# NU-SYNTHS_MIDICV.net
KiCad netlist of a schematic drawn in Altium Designer
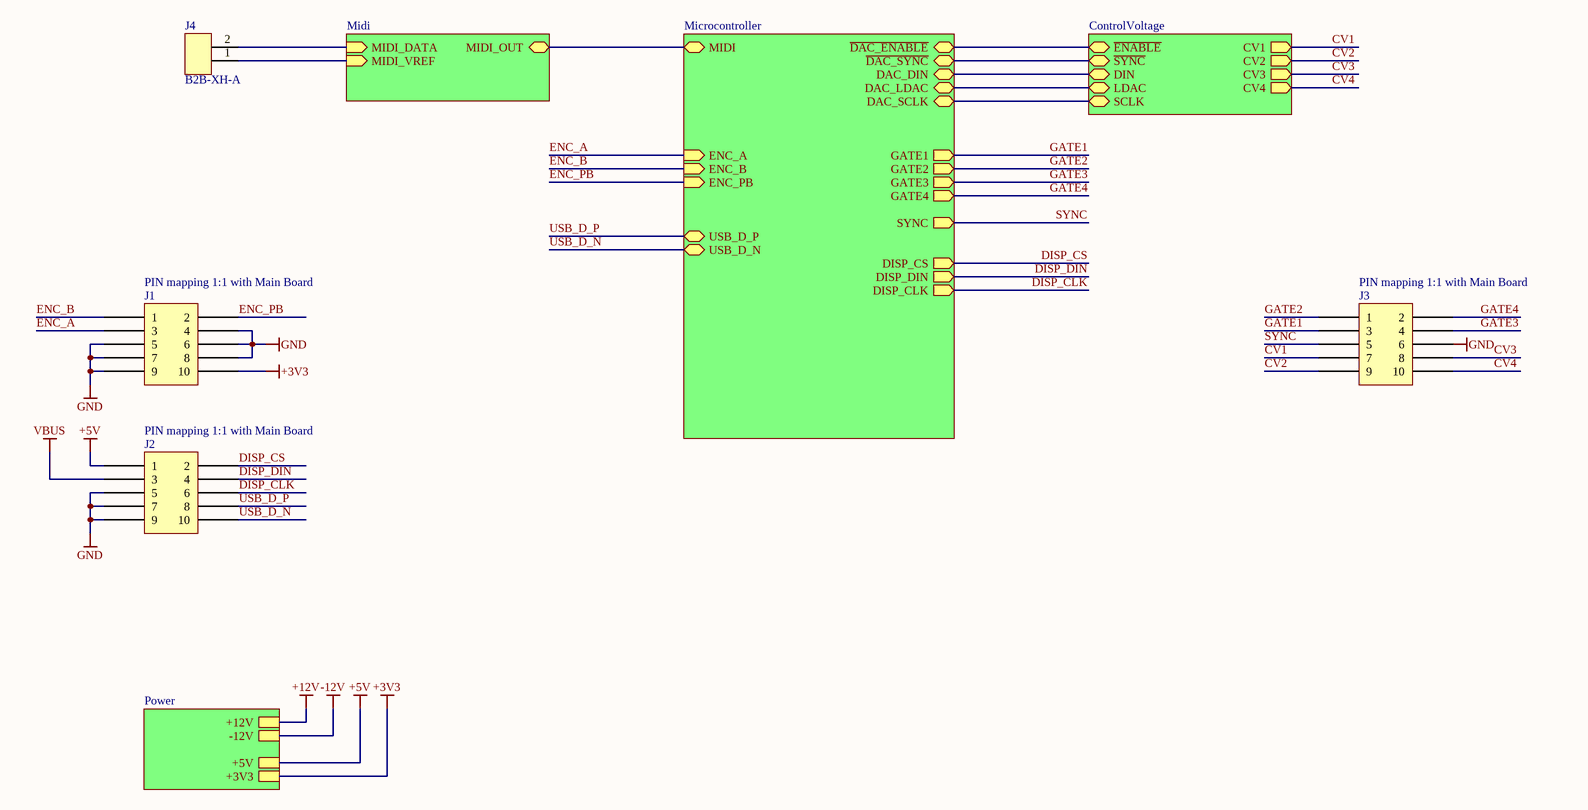
[diagram p0: NU-SYNTHS_MIDICV.SchDoc]

(export (version "E")
  (design (tool "Eeschema 10.0.6"))
  (components
    (comp (ref "J1")
      (value "GENERIC_HEADER_2x5")
      (footprint "HEADER_2x5_TH_FEMALE")
      (description "Generic 2x5 header")
      (libsource (lib "LabratsSynthLib") (part "GENERIC_HEADER_2x5"))
    )
    (comp (ref "J2")
      (value "GENERIC_HEADER_2x5")
      (footprint "HEADER_2x5_TH_FEMALE")
      (description "Generic 2x5 header")
      (libsource (lib "LabratsSynthLib") (part "GENERIC_HEADER_2x5"))
    )
    (comp (ref "J3")
      (value "GENERIC_HEADER_2x5")
      (footprint "HEADER_2x5_TH_FEMALE")
      (description "Generic 2x5 header")
      (libsource (lib "LabratsSynthLib") (part "GENERIC_HEADER_2x5"))
    )
    (comp (ref "J4")
      (value "B2B-XH-A")
      (footprint "JST_HEADER_1x2_SMD_MALE")
      (description "Connector Header Through Hole 2 position 0.098 (2.50mm)")
      (fields (field (name "MF") "JST Sales") (field (name "MP") "B2B-XH-A(LF)(SN)"))
      (libsource (lib "LabratsSynthLib") (part "B2B-XH-A(LF)(SN)"))
    )
  )
  (nets
    (net (code "1") (name "+3V3") (class "Default")
      (node (ref "J1") (pin "10") (pinfunction "10_10") (pintype "passive"))
    )
    (net (code "2") (name "+5V") (class "Default")
      (node (ref "J2") (pin "1") (pinfunction "1_1") (pintype "passive"))
    )
    (net (code "5") (name "/CV1") (class "Default")
      (node (ref "J3") (pin "7") (pinfunction "7_7") (pintype "passive"))
    )
    (net (code "6") (name "/CV2") (class "Default")
      (node (ref "J3") (pin "9") (pinfunction "9_9") (pintype "passive"))
    )
    (net (code "7") (name "/CV3") (class "Default")
      (node (ref "J3") (pin "8") (pinfunction "8_8") (pintype "passive"))
    )
    (net (code "8") (name "/CV4") (class "Default")
      (node (ref "J3") (pin "10") (pinfunction "10_10") (pintype "passive"))
    )
    (net (code "12") (name "/DISP_CLK") (class "Default")
      (node (ref "J2") (pin "6") (pinfunction "6_6") (pintype "passive"))
    )
    (net (code "13") (name "/DISP_CS") (class "Default")
      (node (ref "J2") (pin "2") (pinfunction "2_2") (pintype "passive"))
    )
    (net (code "14") (name "/DISP_DIN") (class "Default")
      (node (ref "J2") (pin "4") (pinfunction "4_4") (pintype "passive"))
    )
    (net (code "15") (name "/ENC_A") (class "Default")
      (node (ref "J1") (pin "3") (pinfunction "3_3") (pintype "passive"))
    )
    (net (code "16") (name "/ENC_B") (class "Default")
      (node (ref "J1") (pin "1") (pinfunction "1_1") (pintype "passive"))
    )
    (net (code "17") (name "/ENC_PB") (class "Default")
      (node (ref "J1") (pin "2") (pinfunction "2_2") (pintype "passive"))
    )
    (net (code "18") (name "/GATE1") (class "Default")
      (node (ref "J3") (pin "3") (pinfunction "3_3") (pintype "passive"))
    )
    (net (code "19") (name "/GATE2") (class "Default")
      (node (ref "J3") (pin "1") (pinfunction "1_1") (pintype "passive"))
    )
    (net (code "20") (name "/GATE3") (class "Default")
      (node (ref "J3") (pin "4") (pinfunction "4_4") (pintype "passive"))
    )
    (net (code "21") (name "/GATE4") (class "Default")
      (node (ref "J3") (pin "2") (pinfunction "2_2") (pintype "passive"))
    )
    (net (code "23") (name "/MIDI_DATA") (class "Default")
      (node (ref "J4") (pin "2") (pinfunction "2_2") (pintype "passive"))
    )
    (net (code "24") (name "/MIDI_VREF") (class "Default")
      (node (ref "J4") (pin "1") (pinfunction "1_1") (pintype "passive"))
    )
    (net (code "25") (name "/SYNC") (class "Default")
      (node (ref "J3") (pin "5") (pinfunction "5_5") (pintype "passive"))
    )
    (net (code "26") (name "/USB_D_N") (class "Default")
      (node (ref "J2") (pin "10") (pinfunction "10_10") (pintype "passive"))
    )
    (net (code "27") (name "/USB_D_P") (class "Default")
      (node (ref "J2") (pin "8") (pinfunction "8_8") (pintype "passive"))
    )
    (net (code "30") (name "GND") (class "Default")
      (node (ref "J1") (pin "4") (pinfunction "4_4") (pintype "passive"))
      (node (ref "J1") (pin "5") (pinfunction "5_5") (pintype "passive"))
      (node (ref "J1") (pin "6") (pinfunction "6_6") (pintype "passive"))
      (node (ref "J1") (pin "7") (pinfunction "7_7") (pintype "passive"))
      (node (ref "J1") (pin "8") (pinfunction "8_8") (pintype "passive"))
      (node (ref "J1") (pin "9") (pinfunction "9_9") (pintype "passive"))
      (node (ref "J2") (pin "5") (pinfunction "5_5") (pintype "passive"))
      (node (ref "J2") (pin "7") (pinfunction "7_7") (pintype "passive"))
      (node (ref "J2") (pin "9") (pinfunction "9_9") (pintype "passive"))
      (node (ref "J3") (pin "6") (pinfunction "6_6") (pintype "passive"))
    )
    (net (code "31") (name "VBUS") (class "Default")
      (node (ref "J2") (pin "3") (pinfunction "3_3") (pintype "passive"))
    )
  )
)
